# GPT_NLP_DC_Board.net
KiCad netlist of a schematic drawn in Altium Designer
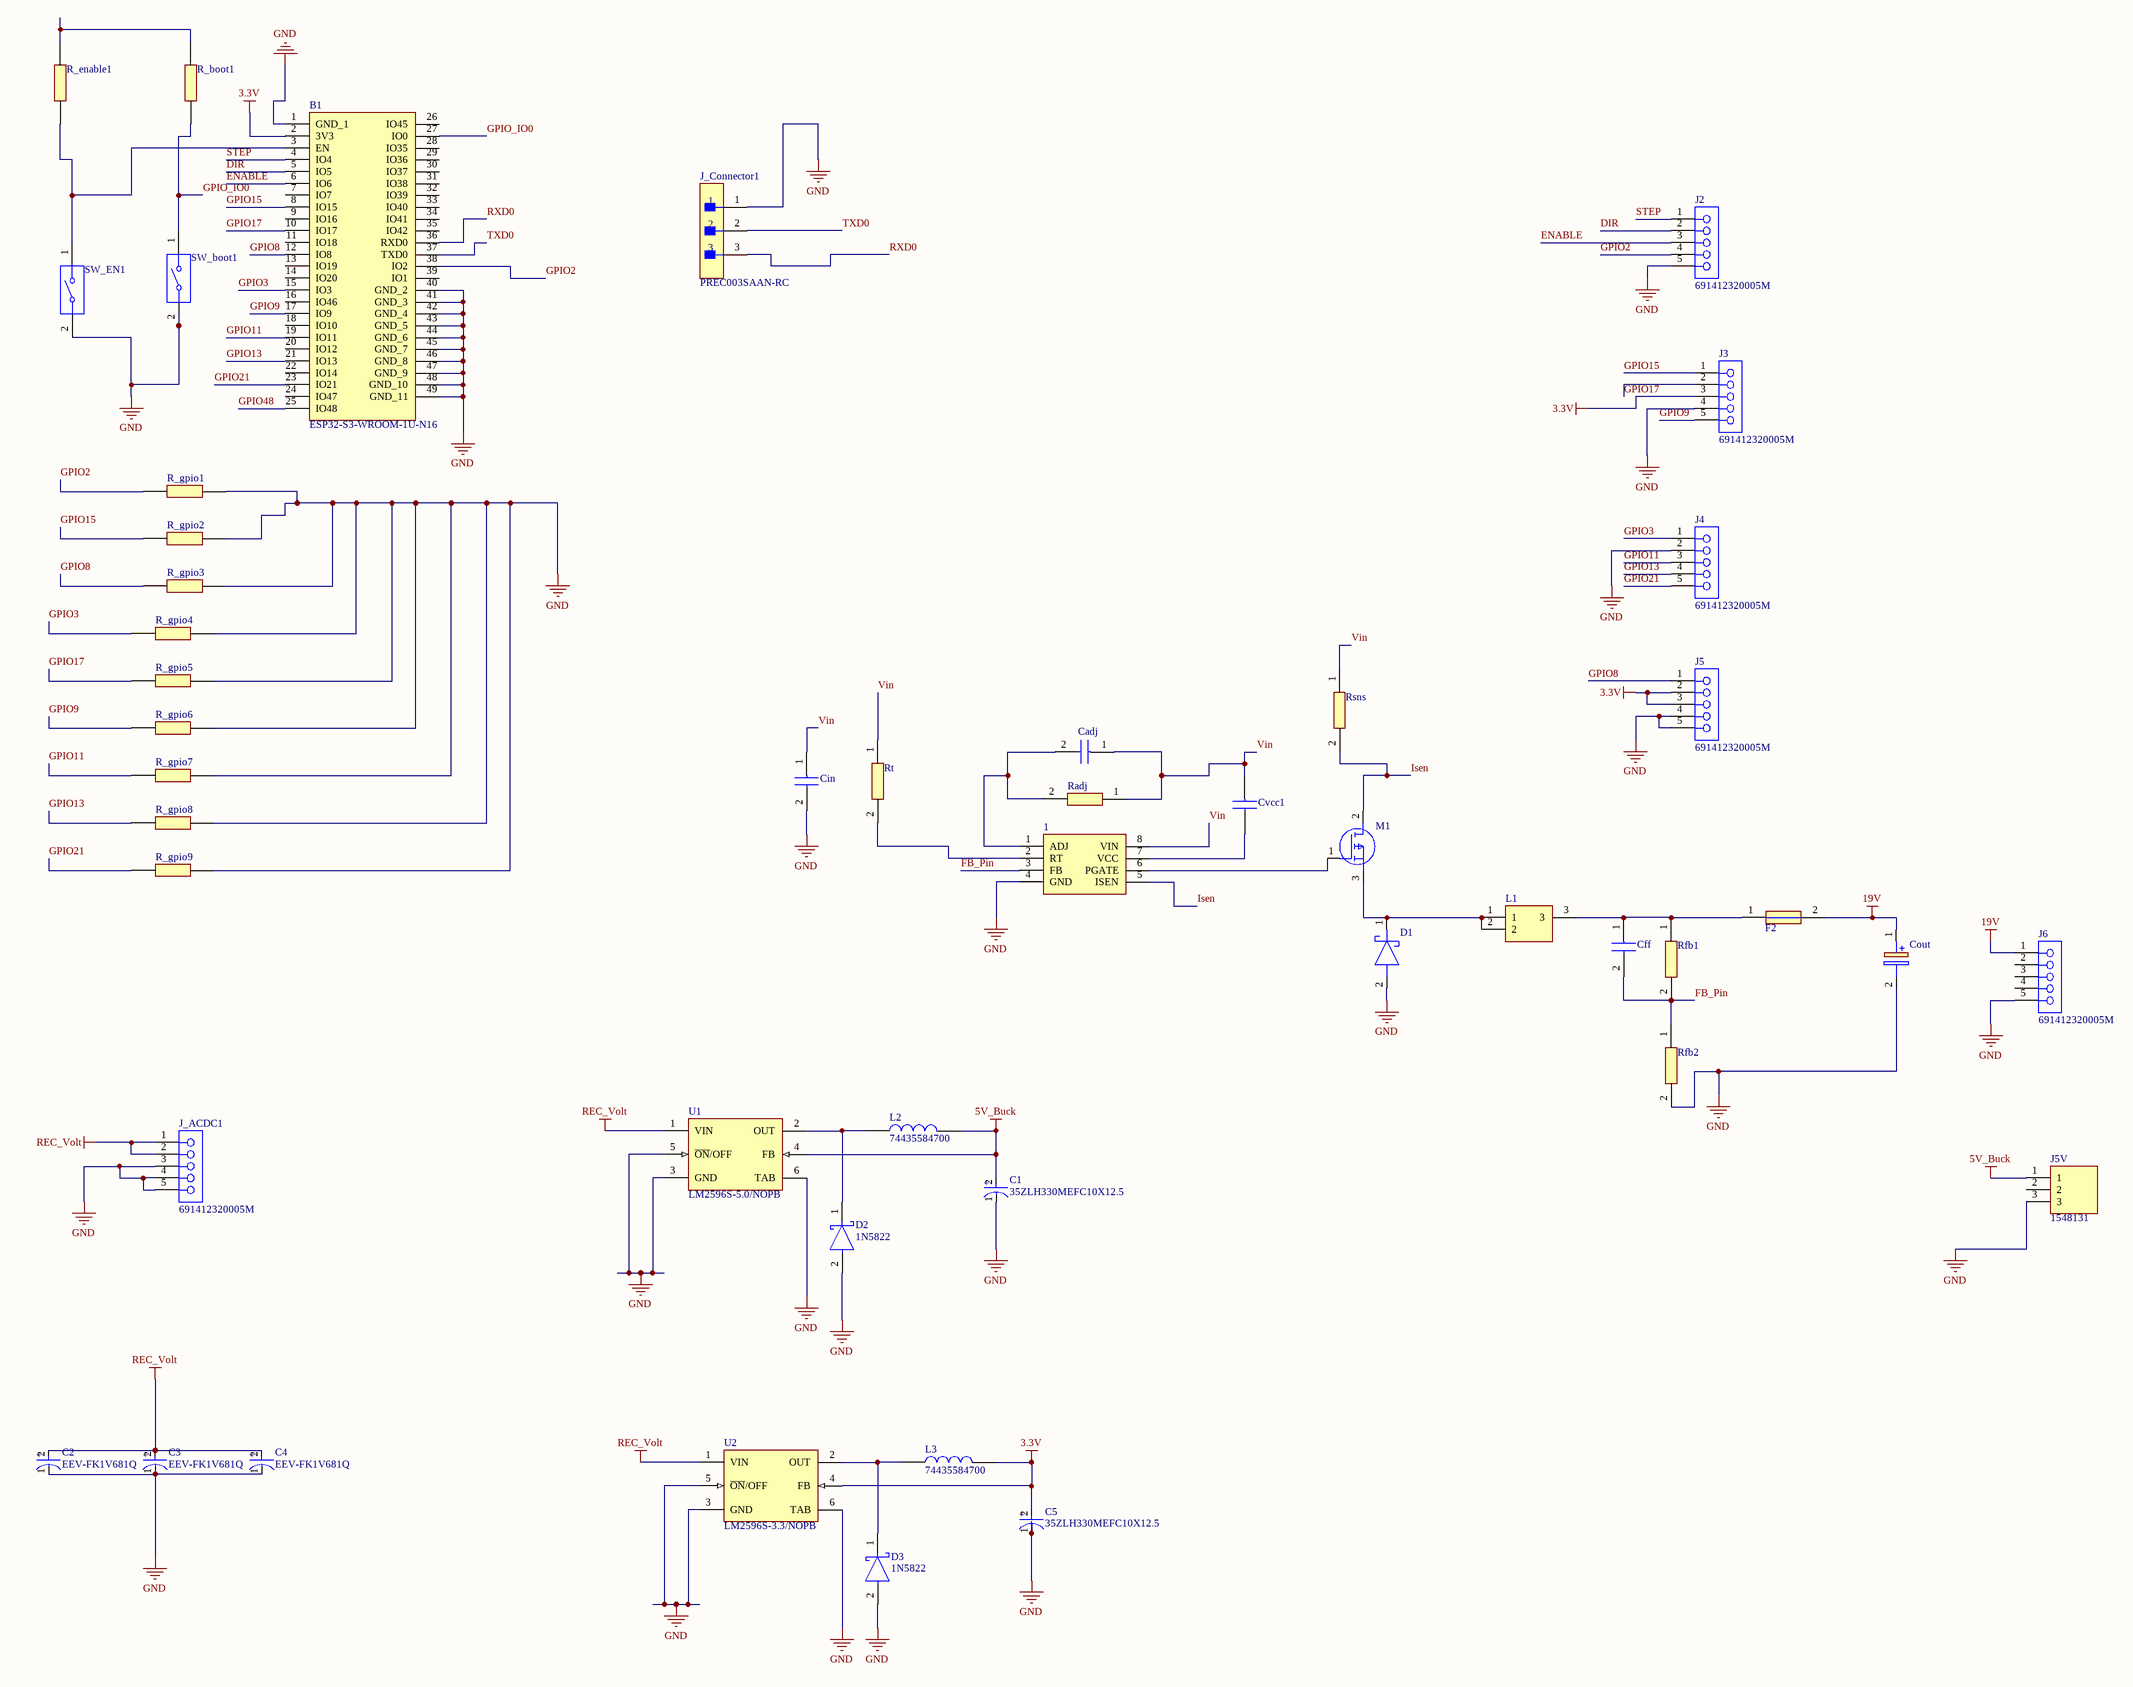
[diagram p0: GPT_NLP_DC Board.SchDoc]

(export (version "E")
  (design (tool "Eeschema 10.0.6"))
  (components
    (comp (ref "1")
      (value "LM25085AMM_NOPB")
      (footprint "SamacSys:SOP65P490X110-8N")
      (description "Integrated Circuit")
      (fields
        (field (name "MANUFACTURER_PART_NUMBER") "LM25085AMM/NOPB")
        (field (name "MOUSER PART NUMBER") "926-LM25085AMM/NOPB")
      )
      (libsource (lib "*") (part "LM25085AMM_NOPB"))
    )
    (comp (ref "B1")
      (value "ESP32-S3-WROOM-1U-N16")
      (footprint "ESP32S3WROOM1UN16")
      (description "Multiprotocol Modules SMD Module, ESP32-S3, 16 MB SPI Flash, IPEX Antenna Connector")
      (fields (field (name "MOUSER PART NUMBER") "356-ESP32S3WROM1UN16"))
      (libsource (lib "ESP32-S3-WROOM-1U-N16") (part "ESP32-S3-WROOM-1U-N16"))
    )
    (comp (ref "C1")
      (value "35ZLH330MEFC10X12.5")
      (footprint "FP-35ZLH330MEFC10X12_5-MFG")
      (fields (field (name "TOLERANCE") "20%") (field (name "VOLTAGE") "35V"))
      (libsource (lib "Altium Content Vault") (part "a00bbbee19879c290e62620ae7e47b1"))
    )
    (comp (ref "C2")
      (value "EEV-FK1V681Q")
      (footprint "FP-FKH13-MFG")
      (description "CAP ALUM 680UF 20% 35V SMD")
      (fields (field (name "VOLTAGE") "35V") (field (name "TOLERANCE") "20%"))
      (libsource (lib "Altium Content Vault") (part "203bc49f2ac43e59fd269a8c329ed05"))
    )
    (comp (ref "C3")
      (value "EEV-FK1V681Q")
      (footprint "FP-FKH13-MFG")
      (description "CAP ALUM 680UF 20% 35V SMD")
      (fields (field (name "VOLTAGE") "35V") (field (name "TOLERANCE") "20%"))
      (libsource (lib "Altium Content Vault") (part "203bc49f2ac43e59fd269a8c329ed05"))
    )
    (comp (ref "C4")
      (value "EEV-FK1V681Q")
      (footprint "FP-FKH13-MFG")
      (description "CAP ALUM 680UF 20% 35V SMD")
      (fields (field (name "VOLTAGE") "35V") (field (name "TOLERANCE") "20%"))
      (libsource (lib "Altium Content Vault") (part "203bc49f2ac43e59fd269a8c329ed05"))
    )
    (comp (ref "C5")
      (value "35ZLH330MEFC10X12.5")
      (footprint "FP-35ZLH330MEFC10X12_5-MFG")
      (fields (field (name "TOLERANCE") "20%") (field (name "VOLTAGE") "35V"))
      (libsource (lib "Altium Content Vault") (part "a00bbbee19879c290e62620ae7e47b1"))
    )
    (comp (ref "Cadj")
      (value "C1206C102K5GACTU")
      (footprint "SamacSys:C1206")
      (description "Capacitor")
      (libsource (lib "*") (part "C1206C102K5GACTU"))
    )
    (comp (ref "Cff")
      (value "~")
      (footprint "SamacSys:C1206")
      (description "Capacitor")
      (fields
        (field (name "MANUFACTURER_PART_NUMBER") "C1206C333K5RACTU")
        (field (name "MOUSER PART NUMBER") "80-C1206C333K5R")
      )
      (libsource (lib "*") (part "C1206C333K5RACTU"))
    )
    (comp (ref "Cin")
      (value "MSASU32MSB5106KPNA01")
      (footprint "SamacSys:CAPC3225X270N")
      (description "Capacitor")
      (libsource (lib "*") (part "MSASU32MSB5106KPNA01"))
    )
    (comp (ref "Cout")
      (value "293D106X9063E2TE3")
      (footprint "SamacSys:CAPPM7343X430N")
      (description "Capacitor Polarised")
      (fields (field (name "MOUSER PART NUMBER") "74-293D106X9063E2TE3"))
      (libsource (lib "*") (part "293D106X9063E2TE3"))
    )
    (comp (ref "Cvcc1")
      (value "TMK212BJ474KD-T")
      (footprint "CAPC2012X95N")
      (description "TAIYO YUDEN - TMK212BJ474KD-T - CERAMIC CAPACITOR 0.47UF, 25V, X5R, 10%, 0805")
      (fields (field (name "MOUSER PART NUMBER") "963-TMK212BJ474KD-T"))
      (libsource (lib "TMK212BJ474KD-T") (part "TMK212BJ474KD-T"))
    )
    (comp (ref "D1")
      (value "SS24FL")
      (footprint "SamacSys:SODFL3617X108N")
      (description "Schottky Diode")
      (fields (field (name "MOUSER PART NUMBER") "512-SS24FL"))
      (libsource (lib "*") (part "SS24FL"))
    )
    (comp (ref "D2")
      (value "1N5822")
      (footprint "FP-DO-201AD-MFG")
      (description "DIODE SCHOTTKY 40V 3A DO201AD")
      (fields
        (field (name "OCTOPART") "https://octopart.com/1n5822-stmicroelectronics-323225")
        (field (name "MANUFACTURER") "STMicroelectronics")
      )
      (libsource (lib "Altium Content Vault") (part "1d6ec82d83fb6aee721767c19dac4b9"))
    )
    (comp (ref "D3")
      (value "1N5822")
      (footprint "FP-DO-201AD-MFG")
      (description "DIODE SCHOTTKY 40V 3A DO201AD")
      (fields
        (field (name "OCTOPART") "https://octopart.com/1n5822-stmicroelectronics-323225")
        (field (name "MANUFACTURER") "STMicroelectronics")
      )
      (libsource (lib "Altium Content Vault") (part "1d6ec82d83fb6aee721767c19dac4b9"))
    )
    (comp (ref "F2")
      (value "0407006.WR")
      (footprint "SamacSys:FUSC3216X98N")
      (description "Fuse")
      (fields (field (name "MOUSER PART NUMBER") "576-0407006.WR"))
      (libsource (lib "*") (part "0407006.WR"))
    )
    (comp (ref "J2")
      (value "691412320005M")
      (footprint "691412320005M")
      (description "Terminal Block, 3.81MM Pitch, 45 Deg, Screwless, 16 -30 AWG, 5 Pins")
      (libsource (lib "Altium Content Vault") (part "TBL - 1R - 05P - Female"))
    )
    (comp (ref "J3")
      (value "691412320005M")
      (footprint "691412320005M")
      (description "Terminal Block, 3.81MM Pitch, 45 Deg, Screwless, 16 -30 AWG, 5 Pins")
      (libsource (lib "Altium Content Vault") (part "TBL - 1R - 05P - Female"))
    )
    (comp (ref "J4")
      (value "691412320005M")
      (footprint "691412320005M")
      (description "Terminal Block, 3.81MM Pitch, 45 Deg, Screwless, 16 -30 AWG, 5 Pins")
      (libsource (lib "Altium Content Vault") (part "TBL - 1R - 05P - Female"))
    )
    (comp (ref "J5")
      (value "691412320005M")
      (footprint "691412320005M")
      (description "Terminal Block, 3.81MM Pitch, 45 Deg, Screwless, 16 -30 AWG, 5 Pins")
      (libsource (lib "Altium Content Vault") (part "TBL - 1R - 05P - Female"))
    )
    (comp (ref "J5V")
      (value "1548131")
      (footprint "1548131")
      (description "Pluggable Terminal Blocks SMKDSN 1,5/ 3-5,08 SPE")
      (fields (field (name "MOUSER PART NUMBER") "651-1548131"))
      (libsource (lib "1548131") (part "1548131"))
    )
    (comp (ref "J6")
      (value "691412320005M")
      (footprint "691412320005M")
      (description "Terminal Block, 3.81MM Pitch, 45 Deg, Screwless, 16 -30 AWG, 5 Pins")
      (libsource (lib "Altium Content Vault") (part "TBL - 1R - 05P - Female"))
    )
    (comp (ref "J_ACDC1")
      (value "691412320005M")
      (footprint "691412320005M")
      (description "Terminal Block, 3.81MM Pitch, 45 Deg, Screwless, 16 -30 AWG, 5 Pins")
      (libsource (lib "Altium Content Vault") (part "TBL - 1R - 05P - Female"))
    )
    (comp (ref "J_Connector1")
      (value "PREC003SAAN-RC")
      (footprint "FP-PREC003SAAN-RC-MFG")
      (description "PREC003SAAN-RC Conn Header Vert 3POS 2.54MM")
      (libsource (lib "Altium Content Vault") (part "0d3f023dd272f625e17a2be33dea85f"))
    )
    (comp (ref "L1")
      (value "SER2915L-153KL")
      (footprint "SamacSys:SER2918H333KL")
      (description "Inductor")
      (fields (field (name "MOUSER PART NUMBER") "994-SER2915L-153KL"))
      (libsource (lib "*") (part "SER2915L-153KL"))
    )
    (comp (ref "L2")
      (value "74435584700")
      (footprint "INDM225220X1240N")
      (fields (field (name "MOUSER PART NUMBER") "710-74435584700"))
      (libsource (lib "74435584700") (part "74435584700"))
    )
    (comp (ref "L3")
      (value "74435584700")
      (footprint "INDM225220X1240N")
      (fields (field (name "MOUSER PART NUMBER") "710-74435584700"))
      (libsource (lib "74435584700") (part "74435584700"))
    )
    (comp (ref "M1")
      (value "SUD50P04-08-GE3")
      (footprint "SamacSys:SIHD3N50DT4GE3")
      (description "MOSFET (P-Channel)")
      (fields (field (name "MOUSER PART NUMBER") "781-SUD50P04-08-GE3"))
      (libsource (lib "*") (part "SUD50P04-08-GE3"))
    )
    (comp (ref "Radj")
      (value "CRCW12062K21FKEA")
      (footprint "SamacSys:RESC3216X60N")
      (description "Resistor")
      (fields (field (name "MOUSER PART NUMBER") "71-CRCW1206-2.21K-E3"))
      (libsource (lib "*") (part "CRCW12062K21FKEA"))
    )
    (comp (ref "Rfb1")
      (value "RC1206FR-0710KL")
      (footprint "SamacSys:RESC3116X65N")
      (description "Resistor")
      (fields (field (name "MOUSER PART NUMBER") "603-RC1206FR-0710KL"))
      (libsource (lib "*") (part "RC1206FR-0710KL"))
    )
    (comp (ref "Rfb2")
      (value "CRCW1206499RFKEA")
      (footprint "SamacSys:RESC3216X60N")
      (description "Resistor")
      (fields (field (name "MOUSER PART NUMBER") "71-CRCW1206-499-E3"))
      (libsource (lib "*") (part "CRCW1206499RFKEA"))
    )
    (comp (ref "Rsns")
      (value "CSR1206FK10L0")
      (footprint "SamacSys:RESC3016X65N")
      (description "Resistor")
      (libsource (lib "*") (part "CSR1206FK10L0"))
    )
    (comp (ref "Rt")
      (value "CRCW1206665KFKEA")
      (footprint "SamacSys:RESC3216X60N")
      (description "Resistor")
      (libsource (lib "*") (part "CRCW1206665KFKEA"))
    )
    (comp (ref "R_boot1")
      (value "CRCW121010K0JNEAIF")
      (footprint "RESC3225X60N")
      (fields (field (name "MOUSER PART NUMBER") "71-CRCW121010K0JNAIF"))
      (libsource (lib "CRCW121010K0JNEAIF") (part "CRCW121010K0JNEAIF"))
    )
    (comp (ref "R_enable1")
      (value "CRCW121010K0JNEAIF")
      (footprint "RESC3225X60N")
      (fields (field (name "MOUSER PART NUMBER") "71-CRCW121010K0JNAIF"))
      (libsource (lib "CRCW121010K0JNEAIF") (part "CRCW121010K0JNEAIF"))
    )
    (comp (ref "R_gpio1")
      (value "CRCW121010K0JNEAIF")
      (footprint "RESC3225X60N")
      (fields (field (name "MOUSER PART NUMBER") "71-CRCW121010K0JNAIF"))
      (libsource (lib "") (part "CRCW121010K0JNEAIF_1"))
    )
    (comp (ref "R_gpio2")
      (value "CRCW121010K0JNEAIF")
      (footprint "RESC3225X60N")
      (fields (field (name "MOUSER PART NUMBER") "71-CRCW121010K0JNAIF"))
      (libsource (lib "") (part "CRCW121010K0JNEAIF_1"))
    )
    (comp (ref "R_gpio3")
      (value "CRCW121010K0JNEAIF")
      (footprint "RESC3225X60N")
      (fields (field (name "MOUSER PART NUMBER") "71-CRCW121010K0JNAIF"))
      (libsource (lib "") (part "CRCW121010K0JNEAIF_1"))
    )
    (comp (ref "R_gpio4")
      (value "CRCW121010K0JNEAIF")
      (footprint "RESC3225X60N")
      (fields (field (name "MOUSER PART NUMBER") "71-CRCW121010K0JNAIF"))
      (libsource (lib "") (part "CRCW121010K0JNEAIF_1"))
    )
    (comp (ref "R_gpio5")
      (value "CRCW121010K0JNEAIF")
      (footprint "RESC3225X60N")
      (fields (field (name "MOUSER PART NUMBER") "71-CRCW121010K0JNAIF"))
      (libsource (lib "") (part "CRCW121010K0JNEAIF_1"))
    )
    (comp (ref "R_gpio6")
      (value "CRCW121010K0JNEAIF")
      (footprint "RESC3225X60N")
      (fields (field (name "MOUSER PART NUMBER") "71-CRCW121010K0JNAIF"))
      (libsource (lib "") (part "CRCW121010K0JNEAIF_1"))
    )
    (comp (ref "R_gpio7")
      (value "CRCW121010K0JNEAIF")
      (footprint "RESC3225X60N")
      (fields (field (name "MOUSER PART NUMBER") "71-CRCW121010K0JNAIF"))
      (libsource (lib "") (part "CRCW121010K0JNEAIF_1"))
    )
    (comp (ref "R_gpio8")
      (value "CRCW121010K0JNEAIF")
      (footprint "RESC3225X60N")
      (fields (field (name "MOUSER PART NUMBER") "71-CRCW121010K0JNAIF"))
      (libsource (lib "") (part "CRCW121010K0JNEAIF_1"))
    )
    (comp (ref "R_gpio9")
      (value "CRCW121010K0JNEAIF")
      (footprint "RESC3225X60N")
      (fields (field (name "MOUSER PART NUMBER") "71-CRCW121010K0JNAIF"))
      (libsource (lib "") (part "CRCW121010K0JNEAIF_1"))
    )
    (comp (ref "SW_boot1")
      (value "MX1A-11NW")
      (footprint "CHRY-MX1A-11NW_V")
      (description "Keylock Switch, 12 V, -10 to 70 degC, 2-Pin THD, RoHS, Bulk")
      (fields (field (name "MANUFACTURER") "Cherry") (field (name "PART NO") "MX1A11NW"))
      (libsource (lib "Altium Content Vault") (part "KEYSW-SPST-2"))
    )
    (comp (ref "SW_EN1")
      (value "MX1A-11NW")
      (footprint "CHRY-MX1A-11NW_V")
      (description "Keylock Switch, 12 V, -10 to 70 degC, 2-Pin THD, RoHS, Bulk")
      (fields (field (name "MANUFACTURER") "Cherry") (field (name "PART NO") "MX1A11NW"))
      (libsource (lib "Altium Content Vault") (part "KEYSW-SPST-2"))
    )
    (comp (ref "U1")
      (value "LM2596S-5.0/NOPB")
      (footprint "KTT0005B_M")
      (description "SIMPLE SWITCHER® Power Converter 150 KHz 3A Step-Down Voltage Regulator, 5-pin TO-263, Pb-Free")
      (fields (field (name "MANUFACTURER") "Texas Instruments"))
      (libsource (lib "Altium Content Vault") (part "PM-REG-LM2575HVS-12"))
    )
    (comp (ref "U2")
      (value "LM2596S-3.3/NOPB")
      (footprint "KTT0005B_M")
      (description "SIMPLE SWITCHER® Power Converter 150 KHz 3A Step-Down Voltage Regulator, 5-pin TO-263, Pb-Free")
      (fields (field (name "MANUFACTURER") "Texas Instruments"))
      (libsource (lib "Altium Content Vault") (part "PM-REG-LM2575HVS-12"))
    )
  )
  (nets
    (net (code "1") (name "/DIR") (class "Default")
      (node (ref "B1") (pin "5") (pinfunction "IO5_5") (pintype "passive"))
      (node (ref "J2") (pin "2") (pinfunction "2_2") (pintype "passive"))
    )
    (net (code "2") (name "/ENABLE") (class "Default")
      (node (ref "B1") (pin "6") (pinfunction "IO6_6") (pintype "passive"))
      (node (ref "J2") (pin "3") (pinfunction "3_3") (pintype "passive"))
    )
    (net (code "3") (name "/FB_Pin") (class "Default")
      (node (ref "1") (pin "3") (pinfunction "FB_3") (pintype "passive"))
      (node (ref "Cff") (pin "2") (pinfunction "2_2") (pintype "passive"))
      (node (ref "Rfb1") (pin "2") (pinfunction "2_2") (pintype "passive"))
      (node (ref "Rfb2") (pin "1") (pinfunction "1_1") (pintype "passive"))
    )
    (net (code "4") (name "/GPIO2") (class "Default")
      (node (ref "B1") (pin "38") (pinfunction "IO2_38") (pintype "passive"))
      (node (ref "J2") (pin "4") (pinfunction "4_4") (pintype "passive"))
      (node (ref "R_gpio1") (pin "1") (pinfunction "1_1") (pintype "passive"))
    )
    (net (code "5") (name "/GPIO3") (class "Default")
      (node (ref "B1") (pin "15") (pinfunction "IO3_15") (pintype "passive"))
      (node (ref "J4") (pin "1") (pinfunction "1_1") (pintype "passive"))
      (node (ref "R_gpio4") (pin "1") (pinfunction "1_1") (pintype "passive"))
    )
    (net (code "6") (name "/GPIO8") (class "Default")
      (node (ref "B1") (pin "12") (pinfunction "IO8_12") (pintype "passive"))
      (node (ref "J5") (pin "1") (pinfunction "1_1") (pintype "passive"))
      (node (ref "R_gpio3") (pin "1") (pinfunction "1_1") (pintype "passive"))
    )
    (net (code "7") (name "/GPIO9") (class "Default")
      (node (ref "B1") (pin "17") (pinfunction "IO9_17") (pintype "passive"))
      (node (ref "J3") (pin "5") (pinfunction "5_5") (pintype "passive"))
      (node (ref "R_gpio6") (pin "1") (pinfunction "1_1") (pintype "passive"))
    )
    (net (code "8") (name "/GPIO11") (class "Default")
      (node (ref "B1") (pin "19") (pinfunction "IO11_19") (pintype "passive"))
      (node (ref "J4") (pin "3") (pinfunction "3_3") (pintype "passive"))
      (node (ref "R_gpio7") (pin "1") (pinfunction "1_1") (pintype "passive"))
    )
    (net (code "9") (name "/GPIO13") (class "Default")
      (node (ref "B1") (pin "21") (pinfunction "IO13_21") (pintype "passive"))
      (node (ref "J4") (pin "4") (pinfunction "4_4") (pintype "passive"))
      (node (ref "R_gpio8") (pin "1") (pinfunction "1_1") (pintype "passive"))
    )
    (net (code "10") (name "/GPIO15") (class "Default")
      (node (ref "B1") (pin "8") (pinfunction "IO15_8") (pintype "passive"))
      (node (ref "J3") (pin "1") (pinfunction "1_1") (pintype "passive"))
      (node (ref "R_gpio2") (pin "1") (pinfunction "1_1") (pintype "passive"))
    )
    (net (code "11") (name "/GPIO17") (class "Default")
      (node (ref "B1") (pin "10") (pinfunction "IO17_10") (pintype "passive"))
      (node (ref "J3") (pin "2") (pinfunction "2_2") (pintype "passive"))
      (node (ref "R_gpio5") (pin "1") (pinfunction "1_1") (pintype "passive"))
    )
    (net (code "12") (name "/GPIO21") (class "Default")
      (node (ref "B1") (pin "23") (pinfunction "IO21_23") (pintype "passive"))
      (node (ref "J4") (pin "5") (pinfunction "5_5") (pintype "passive"))
      (node (ref "R_gpio9") (pin "1") (pinfunction "1_1") (pintype "passive"))
    )
    (net (code "13") (name "/GPIO48") (class "Default")
      (node (ref "B1") (pin "25") (pinfunction "IO48_25") (pintype "passive"))
    )
    (net (code "14") (name "/GPIO_IO0") (class "Default")
      (node (ref "B1") (pin "27") (pinfunction "IO0_27") (pintype "passive"))
      (node (ref "R_boot1") (pin "1") (pinfunction "1_1") (pintype "passive"))
      (node (ref "SW_boot1") (pin "1") (pinfunction "1_1") (pintype "passive"))
    )
    (net (code "15") (name "/Isen") (class "Default")
      (node (ref "1") (pin "5") (pinfunction "ISEN_5") (pintype "passive"))
      (node (ref "M1") (pin "2") (pinfunction "D_2") (pintype "passive"))
      (node (ref "Rsns") (pin "2") (pinfunction "2_2") (pintype "passive"))
    )
    (net (code "16") (name "/RXD0") (class "Default")
      (node (ref "B1") (pin "36") (pinfunction "RXD0_36") (pintype "passive"))
      (node (ref "J_Connector1") (pin "3") (pinfunction "3_3") (pintype "passive"))
    )
    (net (code "17") (name "/STEP") (class "Default")
      (node (ref "B1") (pin "4") (pinfunction "IO4_4") (pintype "passive"))
      (node (ref "J2") (pin "1") (pinfunction "1_1") (pintype "passive"))
    )
    (net (code "18") (name "/TXD0") (class "Default")
      (node (ref "B1") (pin "37") (pinfunction "TXD0_37") (pintype "passive"))
      (node (ref "J_Connector1") (pin "2") (pinfunction "2_2") (pintype "passive"))
    )
    (net (code "19") (name "/Vin") (class "Default")
      (node (ref "1") (pin "8") (pinfunction "VIN_8") (pintype "passive"))
      (node (ref "Cadj") (pin "1") (pinfunction "1_1") (pintype "passive"))
      (node (ref "Cin") (pin "1") (pinfunction "1_1") (pintype "passive"))
      (node (ref "Cvcc1") (pin "2") (pinfunction "2_2") (pintype "passive"))
      (node (ref "Radj") (pin "1") (pinfunction "1_1") (pintype "passive"))
      (node (ref "Rsns") (pin "1") (pinfunction "1_1") (pintype "passive"))
      (node (ref "Rt") (pin "1") (pinfunction "1_1") (pintype "passive"))
    )
    (net (code "20") (name "3.3V") (class "Default")
      (node (ref "B1") (pin "2") (pinfunction "3V3_2") (pintype "passive"))
      (node (ref "C5") (pin "2") (pinfunction "A_2") (pintype "passive"))
      (node (ref "J3") (pin "3") (pinfunction "3_3") (pintype "passive"))
      (node (ref "J5") (pin "2") (pinfunction "2_2") (pintype "passive"))
      (node (ref "J5") (pin "3") (pinfunction "3_3") (pintype "passive"))
      (node (ref "L3") (pin "2") (pinfunction "2_2") (pintype "passive"))
      (node (ref "U2") (pin "4") (pinfunction "FB_4") (pintype "input"))
    )
    (net (code "21") (name "5V_Buck") (class "Default")
      (node (ref "C1") (pin "2") (pinfunction "A_2") (pintype "passive"))
      (node (ref "J5V") (pin "1") (pinfunction "1_1") (pintype "passive"))
      (node (ref "L2") (pin "2") (pinfunction "2_2") (pintype "passive"))
      (node (ref "U1") (pin "4") (pinfunction "FB_4") (pintype "input"))
    )
    (net (code "22") (name "19V") (class "Default")
      (node (ref "Cout") (pin "1") (pinfunction "+_1") (pintype "passive"))
      (node (ref "F2") (pin "2") (pinfunction "2_2") (pintype "passive"))
      (node (ref "J6") (pin "1") (pinfunction "1_1") (pintype "passive"))
    )
    (net (code "23") (name "GND") (class "Default")
      (node (ref "1") (pin "4") (pinfunction "GND_4") (pintype "passive"))
      (node (ref "B1") (pin "1") (pinfunction "GND_1_1") (pintype "passive"))
      (node (ref "B1") (pin "40") (pinfunction "GND_2_40") (pintype "passive"))
      (node (ref "B1") (pin "41") (pinfunction "GND_3_41") (pintype "passive"))
      (node (ref "B1") (pin "42") (pinfunction "GND_4_42") (pintype "passive"))
      (node (ref "B1") (pin "43") (pinfunction "GND_5_43") (pintype "passive"))
      (node (ref "B1") (pin "44") (pinfunction "GND_6_44") (pintype "passive"))
      (node (ref "B1") (pin "45") (pinfunction "GND_7_45") (pintype "passive"))
      (node (ref "B1") (pin "46") (pinfunction "GND_8_46") (pintype "passive"))
      (node (ref "B1") (pin "47") (pinfunction "GND_9_47") (pintype "passive"))
      (node (ref "B1") (pin "48") (pinfunction "GND_10_48") (pintype "passive"))
      (node (ref "B1") (pin "49") (pinfunction "GND_11_49") (pintype "passive"))
      (node (ref "C1") (pin "1") (pinfunction "C_1") (pintype "passive"))
      (node (ref "C2") (pin "1") (pinfunction "C_1") (pintype "passive"))
      (node (ref "C3") (pin "1") (pinfunction "C_1") (pintype "passive"))
      (node (ref "C4") (pin "1") (pinfunction "C_1") (pintype "passive"))
      (node (ref "C5") (pin "1") (pinfunction "C_1") (pintype "passive"))
      (node (ref "Cin") (pin "2") (pinfunction "2_2") (pintype "passive"))
      (node (ref "Cout") (pin "2") (pinfunction "-_2") (pintype "passive"))
      (node (ref "D1") (pin "2") (pinfunction "A_2") (pintype "passive"))
      (node (ref "D2") (pin "2") (pinfunction "A_2") (pintype "passive"))
      (node (ref "D3") (pin "2") (pinfunction "A_2") (pintype "passive"))
      (node (ref "J2") (pin "5") (pinfunction "5_5") (pintype "passive"))
      (node (ref "J3") (pin "4") (pinfunction "4_4") (pintype "passive"))
      (node (ref "J4") (pin "2") (pinfunction "2_2") (pintype "passive"))
      (node (ref "J5") (pin "4") (pinfunction "4_4") (pintype "passive"))
      (node (ref "J5") (pin "5") (pinfunction "5_5") (pintype "passive"))
      (node (ref "J5V") (pin "3") (pinfunction "3_3") (pintype "passive"))
      (node (ref "J6") (pin "5") (pinfunction "5_5") (pintype "passive"))
      (node (ref "J_ACDC1") (pin "3") (pinfunction "3_3") (pintype "passive"))
      (node (ref "J_ACDC1") (pin "4") (pinfunction "4_4") (pintype "passive"))
      (node (ref "J_ACDC1") (pin "5") (pinfunction "5_5") (pintype "passive"))
      (node (ref "J_Connector1") (pin "1") (pinfunction "1_1") (pintype "passive"))
      (node (ref "R_gpio1") (pin "2") (pinfunction "2_2") (pintype "passive"))
      (node (ref "R_gpio2") (pin "2") (pinfunction "2_2") (pintype "passive"))
      (node (ref "R_gpio3") (pin "2") (pinfunction "2_2") (pintype "passive"))
      (node (ref "R_gpio4") (pin "2") (pinfunction "2_2") (pintype "passive"))
      (node (ref "R_gpio5") (pin "2") (pinfunction "2_2") (pintype "passive"))
      (node (ref "R_gpio6") (pin "2") (pinfunction "2_2") (pintype "passive"))
      (node (ref "R_gpio7") (pin "2") (pinfunction "2_2") (pintype "passive"))
      (node (ref "R_gpio8") (pin "2") (pinfunction "2_2") (pintype "passive"))
      (node (ref "R_gpio9") (pin "2") (pinfunction "2_2") (pintype "passive"))
      (node (ref "Rfb2") (pin "2") (pinfunction "2_2") (pintype "passive"))
      (node (ref "SW_EN1") (pin "2") (pinfunction "2_2") (pintype "passive"))
      (node (ref "SW_boot1") (pin "2") (pinfunction "2_2") (pintype "passive"))
      (node (ref "U1") (pin "3") (pinfunction "GND_3") (pintype "power_in"))
      (node (ref "U1") (pin "5") (pinfunction "~{ON}/OFF_5") (pintype "input"))
      (node (ref "U1") (pin "6") (pinfunction "TAB_6") (pintype "power_in"))
      (node (ref "U2") (pin "3") (pinfunction "GND_3") (pintype "power_in"))
      (node (ref "U2") (pin "5") (pinfunction "~{ON}/OFF_5") (pintype "input"))
      (node (ref "U2") (pin "6") (pinfunction "TAB_6") (pintype "power_in"))
    )
    (net (code "24") (name "Net-(1-ADJ)") (class "Default")
      (node (ref "1") (pin "1") (pinfunction "ADJ_1") (pintype "passive"))
      (node (ref "Cadj") (pin "2") (pinfunction "2_2") (pintype "passive"))
      (node (ref "Radj") (pin "2") (pinfunction "2_2") (pintype "passive"))
    )
    (net (code "25") (name "Net-(1-PGATE)") (class "Default")
      (node (ref "1") (pin "6") (pinfunction "PGATE_6") (pintype "passive"))
      (node (ref "M1") (pin "1") (pinfunction "G_1") (pintype "passive"))
    )
    (net (code "26") (name "Net-(1-RT)") (class "Default")
      (node (ref "1") (pin "2") (pinfunction "RT_2") (pintype "passive"))
      (node (ref "Rt") (pin "2") (pinfunction "2_2") (pintype "passive"))
    )
    (net (code "27") (name "Net-(1-VCC)") (class "Default")
      (node (ref "1") (pin "7") (pinfunction "VCC_7") (pintype "passive"))
      (node (ref "Cvcc1") (pin "1") (pinfunction "1_1") (pintype "passive"))
    )
    (net (code "28") (name "Net-(B1-EN)") (class "Default")
      (node (ref "B1") (pin "3") (pinfunction "EN_3") (pintype "passive"))
      (node (ref "R_enable1") (pin "1") (pinfunction "1_1") (pintype "passive"))
      (node (ref "SW_EN1") (pin "1") (pinfunction "1_1") (pintype "passive"))
    )
    (net (code "29") (name "Net-(Cff-Pad1)") (class "Default")
      (node (ref "Cff") (pin "1") (pinfunction "1_1") (pintype "passive"))
      (node (ref "F2") (pin "1") (pinfunction "1_1") (pintype "passive"))
      (node (ref "L1") (pin "3") (pinfunction "3_3") (pintype "passive"))
      (node (ref "Rfb1") (pin "1") (pinfunction "1_1") (pintype "passive"))
    )
    (net (code "30") (name "Net-(D1-K)") (class "Default")
      (node (ref "D1") (pin "1") (pinfunction "K_1") (pintype "passive"))
      (node (ref "L1") (pin "1") (pinfunction "1_1") (pintype "passive"))
      (node (ref "L1") (pin "2") (pinfunction "2_2") (pintype "passive"))
      (node (ref "M1") (pin "3") (pinfunction "S_3") (pintype "passive"))
    )
    (net (code "31") (name "Net-(D2-C)") (class "Default")
      (node (ref "D2") (pin "1") (pinfunction "C_1") (pintype "passive"))
      (node (ref "L2") (pin "1") (pinfunction "1_1") (pintype "passive"))
      (node (ref "U1") (pin "2") (pinfunction "OUT_2") (pintype "power_in"))
    )
    (net (code "32") (name "Net-(D3-C)") (class "Default")
      (node (ref "D3") (pin "1") (pinfunction "C_1") (pintype "passive"))
      (node (ref "L3") (pin "1") (pinfunction "1_1") (pintype "passive"))
      (node (ref "U2") (pin "2") (pinfunction "OUT_2") (pintype "power_in"))
    )
    (net (code "33") (name "Net-(R_boot1-Pad2)") (class "Default")
      (node (ref "R_boot1") (pin "2") (pinfunction "2_2") (pintype "passive"))
      (node (ref "R_enable1") (pin "2") (pinfunction "2_2") (pintype "passive"))
    )
    (net (code "34") (name "REC_Volt") (class "Default")
      (node (ref "C2") (pin "2") (pinfunction "A_2") (pintype "passive"))
      (node (ref "C3") (pin "2") (pinfunction "A_2") (pintype "passive"))
      (node (ref "C4") (pin "2") (pinfunction "A_2") (pintype "passive"))
      (node (ref "J_ACDC1") (pin "1") (pinfunction "1_1") (pintype "passive"))
      (node (ref "J_ACDC1") (pin "2") (pinfunction "2_2") (pintype "passive"))
      (node (ref "U1") (pin "1") (pinfunction "VIN_1") (pintype "power_in"))
      (node (ref "U2") (pin "1") (pinfunction "VIN_1") (pintype "power_in"))
    )
    (net (code "35") (name "unconnected-(B1-IO1-Pad39)") (class "Default")
      (node (ref "B1") (pin "39") (pinfunction "IO1_39") (pintype "passive"))
    )
    (net (code "36") (name "unconnected-(B1-IO7-Pad7)") (class "Default")
      (node (ref "B1") (pin "7") (pinfunction "IO7_7") (pintype "passive"))
    )
    (net (code "37") (name "unconnected-(B1-IO10-Pad18)") (class "Default")
      (node (ref "B1") (pin "18") (pinfunction "IO10_18") (pintype "passive"))
    )
    (net (code "38") (name "unconnected-(B1-IO12-Pad20)") (class "Default")
      (node (ref "B1") (pin "20") (pinfunction "IO12_20") (pintype "passive"))
    )
    (net (code "39") (name "unconnected-(B1-IO14-Pad22)") (class "Default")
      (node (ref "B1") (pin "22") (pinfunction "IO14_22") (pintype "passive"))
    )
    (net (code "40") (name "unconnected-(B1-IO16-Pad9)") (class "Default")
      (node (ref "B1") (pin "9") (pinfunction "IO16_9") (pintype "passive"))
    )
    (net (code "41") (name "unconnected-(B1-IO18-Pad11)") (class "Default")
      (node (ref "B1") (pin "11") (pinfunction "IO18_11") (pintype "passive"))
    )
    (net (code "42") (name "unconnected-(B1-IO19-Pad13)") (class "Default")
      (node (ref "B1") (pin "13") (pinfunction "IO19_13") (pintype "passive"))
    )
    (net (code "43") (name "unconnected-(B1-IO20-Pad14)") (class "Default")
      (node (ref "B1") (pin "14") (pinfunction "IO20_14") (pintype "passive"))
    )
    (net (code "44") (name "unconnected-(B1-IO35-Pad28)") (class "Default")
      (node (ref "B1") (pin "28") (pinfunction "IO35_28") (pintype "passive"))
    )
    (net (code "45") (name "unconnected-(B1-IO36-Pad29)") (class "Default")
      (node (ref "B1") (pin "29") (pinfunction "IO36_29") (pintype "passive"))
    )
    (net (code "46") (name "unconnected-(B1-IO37-Pad30)") (class "Default")
      (node (ref "B1") (pin "30") (pinfunction "IO37_30") (pintype "passive"))
    )
    (net (code "47") (name "unconnected-(B1-IO38-Pad31)") (class "Default")
      (node (ref "B1") (pin "31") (pinfunction "IO38_31") (pintype "passive"))
    )
    (net (code "48") (name "unconnected-(B1-IO39-Pad32)") (class "Default")
      (node (ref "B1") (pin "32") (pinfunction "IO39_32") (pintype "passive"))
    )
    (net (code "49") (name "unconnected-(B1-IO40-Pad33)") (class "Default")
      (node (ref "B1") (pin "33") (pinfunction "IO40_33") (pintype "passive"))
    )
    (net (code "50") (name "unconnected-(B1-IO41-Pad34)") (class "Default")
      (node (ref "B1") (pin "34") (pinfunction "IO41_34") (pintype "passive"))
    )
    (net (code "51") (name "unconnected-(B1-IO42-Pad35)") (class "Default")
      (node (ref "B1") (pin "35") (pinfunction "IO42_35") (pintype "passive"))
    )
    (net (code "52") (name "unconnected-(B1-IO45-Pad26)") (class "Default")
      (node (ref "B1") (pin "26") (pinfunction "IO45_26") (pintype "passive"))
    )
    (net (code "53") (name "unconnected-(B1-IO46-Pad16)") (class "Default")
      (node (ref "B1") (pin "16") (pinfunction "IO46_16") (pintype "passive"))
    )
    (net (code "54") (name "unconnected-(B1-IO47-Pad24)") (class "Default")
      (node (ref "B1") (pin "24") (pinfunction "IO47_24") (pintype "passive"))
    )
    (net (code "55") (name "unconnected-(J5V-Pad2)") (class "Default")
      (node (ref "J5V") (pin "2") (pinfunction "2_2") (pintype "passive"))
    )
    (net (code "56") (name "unconnected-(J6-Pad2)") (class "Default")
      (node (ref "J6") (pin "2") (pinfunction "2_2") (pintype "passive"))
    )
    (net (code "57") (name "unconnected-(J6-Pad3)") (class "Default")
      (node (ref "J6") (pin "3") (pinfunction "3_3") (pintype "passive"))
    )
    (net (code "58") (name "unconnected-(J6-Pad4)") (class "Default")
      (node (ref "J6") (pin "4") (pinfunction "4_4") (pintype "passive"))
    )
  )
)
